# simple-loop-activevrs.net
KiCad netlist of a schematic drawn in EAGLE
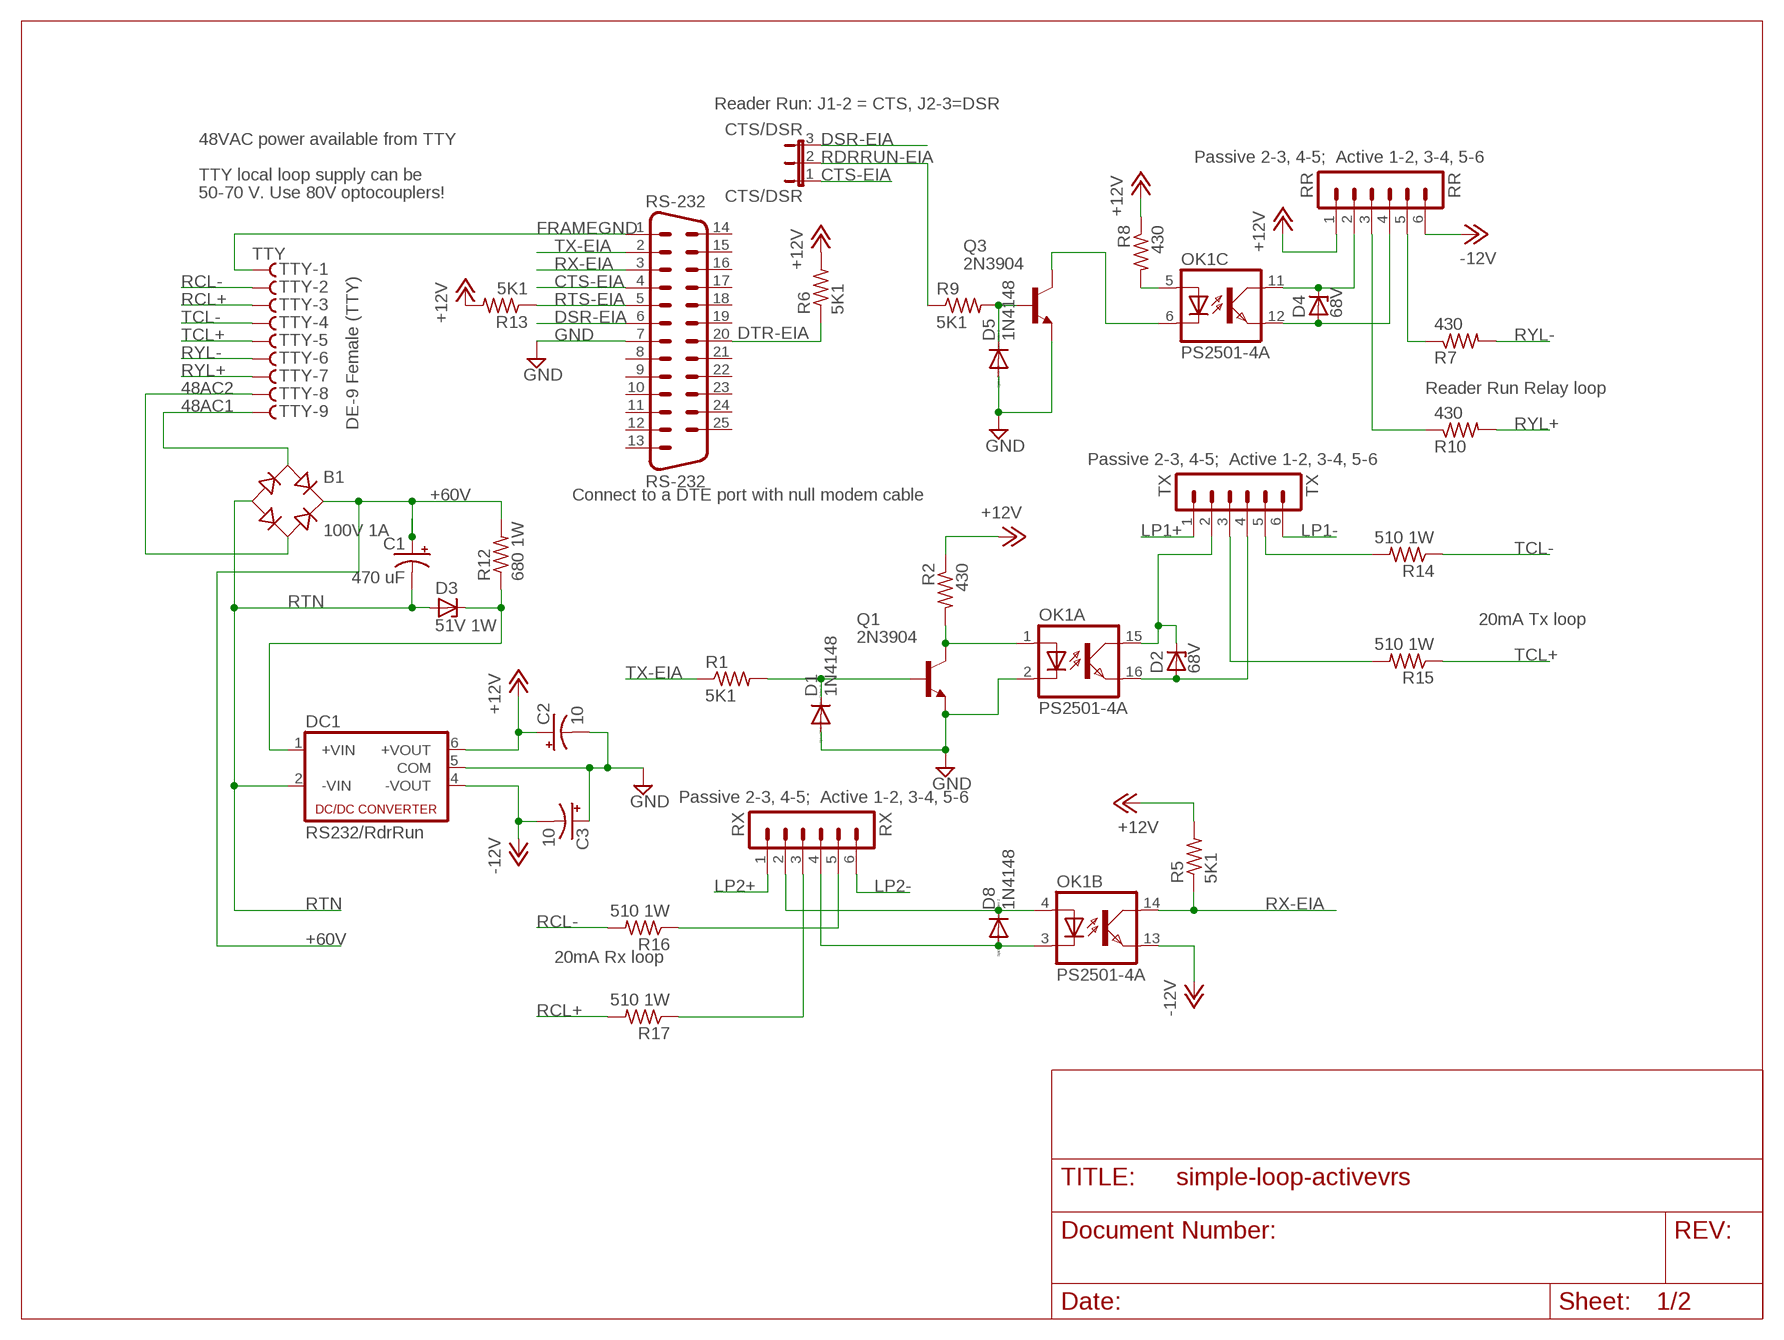
[diagram p0: schematic, sheet 1]
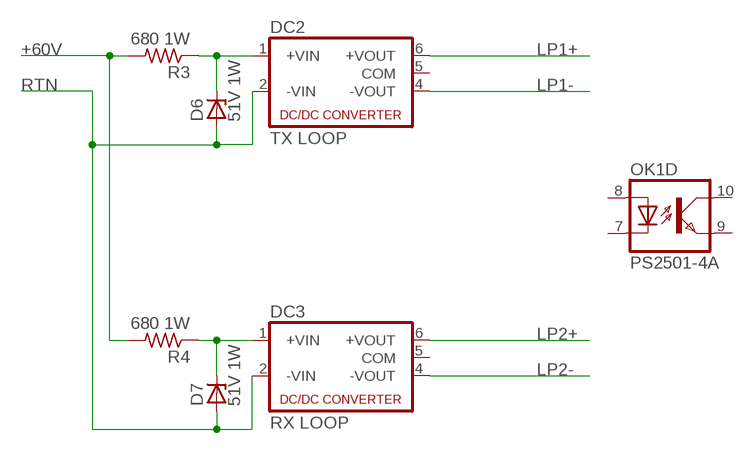
[diagram p1: schematic, sheet 2]

(export (version "E")
  (design (tool "Eeschema 10.0.6"))
  (components
    (comp (ref "D6")
      (value "51V 1W")
      (footprint "eagle-import:DO41Z10")
      (libsource (lib "eagle-import") (part "ZENER-DIODEDO41Z10"))
    )
    (comp (ref "D7")
      (value "51V 1W")
      (footprint "eagle-import:DO41Z10")
      (libsource (lib "eagle-import") (part "ZENER-DIODEDO41Z10"))
    )
    (comp (ref "DC2")
      (value "TX LOOP")
      (footprint "eagle-import:NMA")
      (fields (field (name "MF") "C & D TECHNOLOGIES, INC") (field (name "MPN") "NMA0515SC"))
      (libsource (lib "eagle-import") (part "NMA"))
    )
    (comp (ref "DC3")
      (value "RX LOOP")
      (footprint "eagle-import:NMA")
      (fields (field (name "MF") "C & D TECHNOLOGIES, INC") (field (name "MPN") "NMA0515SC"))
      (libsource (lib "eagle-import") (part "NMA"))
    )
    (comp (ref "OK1")
      (value "PS2501-4A")
      (footprint "eagle-import:DIL16")
      (fields (field (name "MF") "VISHAY/TELEFUNKEN") (field (name "MPN") "ILQ1"))
      (libsource (lib "eagle-import") (part "ILQ1"))
    )
    (comp (ref "R3")
      (value "680 1W")
      (footprint "eagle-import:P0817V")
      (libsource (lib "eagle-import") (part "R-US_0817/7V"))
    )
    (comp (ref "R4")
      (value "680 1W")
      (footprint "eagle-import:P0817V")
      (libsource (lib "eagle-import") (part "R-US_0817/7V"))
    )
    (comp (ref "B1")
      (value "100V 1A")
      (footprint "eagle-import:RB1A")
      (libsource (lib "eagle-import") (part "RB1A"))
    )
    (comp (ref "C1")
      (value "470 uF")
      (footprint "eagle-import:E7,5-18")
      (libsource (lib "eagle-import") (part "CPOL-USE7.5-18"))
    )
    (comp (ref "C2")
      (value "10")
      (footprint "eagle-import:B45181A")
      (libsource (lib "eagle-import") (part "CPOL-USB45181A"))
    )
    (comp (ref "C3")
      (value "10")
      (footprint "eagle-import:B45181A")
      (libsource (lib "eagle-import") (part "CPOL-USB45181A"))
    )
    (comp (ref "CTS/DSR")
      (value "CTS/DSR")
      (footprint "eagle-import:JP2")
      (libsource (lib "eagle-import") (part "JP2E"))
    )
    (comp (ref "D1")
      (value "1N4148")
      (footprint "eagle-import:DO35-10")
      (libsource (lib "eagle-import") (part "1N4148DO35-10"))
    )
    (comp (ref "D2")
      (value "68V")
      (footprint "eagle-import:DO41Z10")
      (libsource (lib "eagle-import") (part "ZENER-DIODEDO41Z10"))
    )
    (comp (ref "D3")
      (value "51V 1W")
      (footprint "eagle-import:DO41Z10")
      (libsource (lib "eagle-import") (part "ZENER-DIODEDO41Z10"))
    )
    (comp (ref "D4")
      (value "68V")
      (footprint "eagle-import:DO41Z10")
      (libsource (lib "eagle-import") (part "ZENER-DIODEDO41Z10"))
    )
    (comp (ref "D5")
      (value "1N4148")
      (footprint "eagle-import:DO35-10")
      (libsource (lib "eagle-import") (part "1N4148DO35-10"))
    )
    (comp (ref "D8")
      (value "1N4148")
      (footprint "eagle-import:DO35-10")
      (libsource (lib "eagle-import") (part "1N4148DO35-10"))
    )
    (comp (ref "DC1")
      (value "RS232/RdrRun")
      (footprint "eagle-import:NMA")
      (fields (field (name "MF") "C & D TECHNOLOGIES, INC") (field (name "MPN") "NMA0515SC"))
      (libsource (lib "eagle-import") (part "NMA"))
    )
    (comp (ref "Q1")
      (value "2N3904")
      (footprint "eagle-import:TO92")
      (libsource (lib "eagle-import") (part "2N3904"))
    )
    (comp (ref "Q3")
      (value "2N3904")
      (footprint "eagle-import:TO92")
      (libsource (lib "eagle-import") (part "2N3904"))
    )
    (comp (ref "R1")
      (value "5K1")
      (footprint "eagle-import:0207_10")
      (libsource (lib "eagle-import") (part "R-US_0207/10"))
    )
    (comp (ref "R2")
      (value "430")
      (footprint "eagle-import:0207_10")
      (libsource (lib "eagle-import") (part "R-US_0207/10"))
    )
    (comp (ref "R5")
      (value "5K1")
      (footprint "eagle-import:0207_10")
      (libsource (lib "eagle-import") (part "R-US_0207/10"))
    )
    (comp (ref "R6")
      (value "5K1")
      (footprint "eagle-import:0207_10")
      (libsource (lib "eagle-import") (part "R-US_0207/10"))
    )
    (comp (ref "R7")
      (value "430")
      (footprint "eagle-import:0207_10")
      (libsource (lib "eagle-import") (part "R-US_0207/10"))
    )
    (comp (ref "R8")
      (value "430")
      (footprint "eagle-import:0207_10")
      (libsource (lib "eagle-import") (part "R-US_0207/10"))
    )
    (comp (ref "R9")
      (value "5K1")
      (footprint "eagle-import:0207_10")
      (libsource (lib "eagle-import") (part "R-US_0207/10"))
    )
    (comp (ref "R10")
      (value "430")
      (footprint "eagle-import:0207_10")
      (libsource (lib "eagle-import") (part "R-US_0207/10"))
    )
    (comp (ref "R12")
      (value "680 1W")
      (footprint "eagle-import:P0817V")
      (libsource (lib "eagle-import") (part "R-US_0817/7V"))
    )
    (comp (ref "R13")
      (value "5K1")
      (footprint "eagle-import:0207_10")
      (libsource (lib "eagle-import") (part "R-US_0207/10"))
    )
    (comp (ref "R14")
      (value "510 1W")
      (footprint "eagle-import:P0817V")
      (libsource (lib "eagle-import") (part "R-US_0817/7V"))
    )
    (comp (ref "R15")
      (value "510 1W")
      (footprint "eagle-import:P0817V")
      (libsource (lib "eagle-import") (part "R-US_0817/7V"))
    )
    (comp (ref "R16")
      (value "510 1W")
      (footprint "eagle-import:P0817V")
      (libsource (lib "eagle-import") (part "R-US_0817/7V"))
    )
    (comp (ref "R17")
      (value "510 1W")
      (footprint "eagle-import:P0817V")
      (libsource (lib "eagle-import") (part "R-US_0817/7V"))
    )
    (comp (ref "RR")
      (value "RR")
      (footprint "eagle-import:MA06-1")
      (libsource (lib "eagle-import") (part "MA06-1"))
    )
    (comp (ref "RS-232")
      (value "RS-232")
      (footprint "eagle-import:M25H")
      (libsource (lib "eagle-import") (part "M25H"))
    )
    (comp (ref "RX")
      (value "RX")
      (footprint "eagle-import:MA06-1")
      (libsource (lib "eagle-import") (part "MA06-1"))
    )
    (comp (ref "TTY")
      (value "TTY")
      (footprint "eagle-import:F09H")
      (libsource (lib "eagle-import") (part "F09?SH"))
    )
    (comp (ref "TX")
      (value "TX")
      (footprint "eagle-import:MA06-1")
      (libsource (lib "eagle-import") (part "MA06-1"))
    )
  )
  (nets
    (net (code "1") (name "+12V") (class "Default")
      (node (ref "C2") (pin "+") (pinfunction "+_+") (pintype "passive"))
      (node (ref "DC1") (pin "6") (pinfunction "+VOUT_6") (pintype "passive"))
      (node (ref "R13") (pin "2") (pinfunction "2_2") (pintype "passive"))
      (node (ref "R2") (pin "1") (pinfunction "1_1") (pintype "passive"))
      (node (ref "R5") (pin "2") (pinfunction "2_2") (pintype "passive"))
      (node (ref "R6") (pin "2") (pinfunction "2_2") (pintype "passive"))
      (node (ref "R8") (pin "1") (pinfunction "1_1") (pintype "passive"))
      (node (ref "RR") (pin "1") (pinfunction "1_1") (pintype "passive"))
    )
    (net (code "2") (name "+60V") (class "Default")
      (node (ref "B1") (pin "+") (pinfunction "+_+") (pintype "passive"))
      (node (ref "C1") (pin "+") (pinfunction "+_+") (pintype "passive"))
      (node (ref "R12") (pin "2") (pinfunction "2_2") (pintype "passive"))
      (node (ref "R3") (pin "2") (pinfunction "2_2") (pintype "passive"))
      (node (ref "R4") (pin "2") (pinfunction "2_2") (pintype "passive"))
    )
    (net (code "3") (name "-12V") (class "Default")
      (node (ref "C3") (pin "-") (pinfunction "-_-") (pintype "passive"))
      (node (ref "DC1") (pin "4") (pinfunction "-VOUT_4") (pintype "passive"))
      (node (ref "OK1") (pin "13") (pinfunction "EMIT_13") (pintype "passive"))
      (node (ref "RR") (pin "6") (pinfunction "6_6") (pintype "passive"))
    )
    (net (code "4") (name "48AC1") (class "Default")
      (node (ref "B1") (pin "AC1") (pinfunction "AC1_AC1") (pintype "passive"))
      (node (ref "TTY") (pin "9") (pinfunction "F_9") (pintype "passive"))
    )
    (net (code "5") (name "48AC2") (class "Default")
      (node (ref "B1") (pin "AC2") (pinfunction "AC2_AC2") (pintype "passive"))
      (node (ref "TTY") (pin "8") (pinfunction "F_8") (pintype "passive"))
    )
    (net (code "6") (name "CTS-EIA") (class "Default")
      (node (ref "CTS/DSR") (pin "1") (pinfunction "1_1") (pintype "passive"))
      (node (ref "RS-232") (pin "4") (pinfunction "4_4") (pintype "passive"))
    )
    (net (code "7") (name "DSR-EIA") (class "Default")
      (node (ref "CTS/DSR") (pin "3") (pinfunction "3_3") (pintype "passive"))
      (node (ref "RS-232") (pin "6") (pinfunction "6_6") (pintype "passive"))
    )
    (net (code "8") (name "DTR-EIA") (class "Default")
      (node (ref "R6") (pin "1") (pinfunction "1_1") (pintype "passive"))
      (node (ref "RS-232") (pin "20") (pinfunction "20_20") (pintype "passive"))
    )
    (net (code "9") (name "FRAMEGND") (class "Default")
      (node (ref "RS-232") (pin "1") (pinfunction "1_1") (pintype "passive"))
      (node (ref "TTY") (pin "1") (pinfunction "F_1") (pintype "passive"))
    )
    (net (code "10") (name "GND") (class "Default")
      (node (ref "C2") (pin "-") (pinfunction "-_-") (pintype "passive"))
      (node (ref "C3") (pin "+") (pinfunction "+_+") (pintype "passive"))
      (node (ref "D1") (pin "A") (pinfunction "A_A") (pintype "passive"))
      (node (ref "D5") (pin "A") (pinfunction "A_A") (pintype "passive"))
      (node (ref "DC1") (pin "5") (pinfunction "COM_5") (pintype "passive"))
      (node (ref "OK1") (pin "2") (pinfunction "C_2") (pintype "passive"))
      (node (ref "Q1") (pin "3") (pinfunction "E_3") (pintype "passive"))
      (node (ref "Q3") (pin "3") (pinfunction "E_3") (pintype "passive"))
      (node (ref "RS-232") (pin "7") (pinfunction "7_7") (pintype "passive"))
    )
    (net (code "11") (name "LP1+") (class "Default")
      (node (ref "DC2") (pin "6") (pinfunction "+VOUT_6") (pintype "passive"))
      (node (ref "TX") (pin "1") (pinfunction "1_1") (pintype "passive"))
    )
    (net (code "12") (name "LP1-") (class "Default")
      (node (ref "DC2") (pin "4") (pinfunction "-VOUT_4") (pintype "passive"))
      (node (ref "TX") (pin "6") (pinfunction "6_6") (pintype "passive"))
    )
    (net (code "13") (name "LP2+") (class "Default")
      (node (ref "DC3") (pin "6") (pinfunction "+VOUT_6") (pintype "passive"))
      (node (ref "RX") (pin "1") (pinfunction "1_1") (pintype "passive"))
    )
    (net (code "14") (name "LP2-") (class "Default")
      (node (ref "DC3") (pin "4") (pinfunction "-VOUT_4") (pintype "passive"))
      (node (ref "RX") (pin "6") (pinfunction "6_6") (pintype "passive"))
    )
    (net (code "15") (name "Net-(DC1-+VIN)") (class "Default")
      (node (ref "D3") (pin "C") (pinfunction "C_C") (pintype "passive"))
      (node (ref "DC1") (pin "1") (pinfunction "+VIN_1") (pintype "passive"))
      (node (ref "R12") (pin "1") (pinfunction "1_1") (pintype "passive"))
    )
    (net (code "16") (name "Net-(DC2-+VIN)") (class "Default")
      (node (ref "D6") (pin "C") (pinfunction "C_C") (pintype "passive"))
      (node (ref "DC2") (pin "1") (pinfunction "+VIN_1") (pintype "passive"))
      (node (ref "R3") (pin "1") (pinfunction "1_1") (pintype "passive"))
    )
    (net (code "17") (name "Net-(DC3-+VIN)") (class "Default")
      (node (ref "D7") (pin "C") (pinfunction "C_C") (pintype "passive"))
      (node (ref "DC3") (pin "1") (pinfunction "+VIN_1") (pintype "passive"))
      (node (ref "R4") (pin "1") (pinfunction "1_1") (pintype "passive"))
    )
    (net (code "18") (name "Net-(OK1A-A)") (class "Default")
      (node (ref "OK1") (pin "1") (pinfunction "A_1") (pintype "passive"))
      (node (ref "Q1") (pin "1") (pinfunction "C_1") (pintype "passive"))
      (node (ref "R2") (pin "2") (pinfunction "2_2") (pintype "passive"))
    )
    (net (code "19") (name "Net-(OK1A-COL)") (class "Default")
      (node (ref "D2") (pin "C") (pinfunction "C_C") (pintype "passive"))
      (node (ref "OK1") (pin "15") (pinfunction "COL_15") (pintype "passive"))
      (node (ref "TX") (pin "2") (pinfunction "2_2") (pintype "passive"))
    )
    (net (code "20") (name "Net-(OK1A-EMIT)") (class "Default")
      (node (ref "D2") (pin "A") (pinfunction "A_A") (pintype "passive"))
      (node (ref "OK1") (pin "16") (pinfunction "EMIT_16") (pintype "passive"))
      (node (ref "TX") (pin "4") (pinfunction "4_4") (pintype "passive"))
    )
    (net (code "21") (name "Net-(OK1B-A)") (class "Default")
      (node (ref "D8") (pin "C") (pinfunction "C_C") (pintype "passive"))
      (node (ref "OK1") (pin "4") (pinfunction "A_4") (pintype "passive"))
      (node (ref "RX") (pin "2") (pinfunction "2_2") (pintype "passive"))
    )
    (net (code "22") (name "Net-(OK1B-C)") (class "Default")
      (node (ref "D8") (pin "A") (pinfunction "A_A") (pintype "passive"))
      (node (ref "OK1") (pin "3") (pinfunction "C_3") (pintype "passive"))
      (node (ref "RX") (pin "4") (pinfunction "4_4") (pintype "passive"))
    )
    (net (code "23") (name "Net-(OK1C-A)") (class "Default")
      (node (ref "OK1") (pin "5") (pinfunction "A_5") (pintype "passive"))
      (node (ref "R8") (pin "2") (pinfunction "2_2") (pintype "passive"))
    )
    (net (code "24") (name "Net-(OK1C-C)") (class "Default")
      (node (ref "OK1") (pin "6") (pinfunction "C_6") (pintype "passive"))
      (node (ref "Q3") (pin "1") (pinfunction "C_1") (pintype "passive"))
    )
    (net (code "25") (name "Net-(OK1C-COL)") (class "Default")
      (node (ref "D4") (pin "C") (pinfunction "C_C") (pintype "passive"))
      (node (ref "OK1") (pin "11") (pinfunction "COL_11") (pintype "passive"))
      (node (ref "RR") (pin "2") (pinfunction "2_2") (pintype "passive"))
    )
    (net (code "26") (name "Net-(OK1C-EMIT)") (class "Default")
      (node (ref "D4") (pin "A") (pinfunction "A_A") (pintype "passive"))
      (node (ref "OK1") (pin "12") (pinfunction "EMIT_12") (pintype "passive"))
      (node (ref "RR") (pin "4") (pinfunction "4_4") (pintype "passive"))
    )
    (net (code "27") (name "Net-(Q1-B)") (class "Default")
      (node (ref "D1") (pin "C") (pinfunction "C_C") (pintype "passive"))
      (node (ref "Q1") (pin "2") (pinfunction "B_2") (pintype "passive"))
      (node (ref "R1") (pin "2") (pinfunction "2_2") (pintype "passive"))
    )
    (net (code "28") (name "Net-(Q3-B)") (class "Default")
      (node (ref "D5") (pin "C") (pinfunction "C_C") (pintype "passive"))
      (node (ref "Q3") (pin "2") (pinfunction "B_2") (pintype "passive"))
      (node (ref "R9") (pin "2") (pinfunction "2_2") (pintype "passive"))
    )
    (net (code "29") (name "Net-(R7-Pad1)") (class "Default")
      (node (ref "R7") (pin "1") (pinfunction "1_1") (pintype "passive"))
      (node (ref "RR") (pin "5") (pinfunction "5_5") (pintype "passive"))
    )
    (net (code "30") (name "Net-(R10-Pad1)") (class "Default")
      (node (ref "R10") (pin "1") (pinfunction "1_1") (pintype "passive"))
      (node (ref "RR") (pin "3") (pinfunction "3_3") (pintype "passive"))
    )
    (net (code "31") (name "Net-(R14-Pad2)") (class "Default")
      (node (ref "R14") (pin "2") (pinfunction "2_2") (pintype "passive"))
      (node (ref "TX") (pin "5") (pinfunction "5_5") (pintype "passive"))
    )
    (net (code "32") (name "Net-(R15-Pad2)") (class "Default")
      (node (ref "R15") (pin "2") (pinfunction "2_2") (pintype "passive"))
      (node (ref "TX") (pin "3") (pinfunction "3_3") (pintype "passive"))
    )
    (net (code "33") (name "Net-(R16-Pad1)") (class "Default")
      (node (ref "R16") (pin "1") (pinfunction "1_1") (pintype "passive"))
      (node (ref "RX") (pin "5") (pinfunction "5_5") (pintype "passive"))
    )
    (net (code "34") (name "Net-(R17-Pad1)") (class "Default")
      (node (ref "R17") (pin "1") (pinfunction "1_1") (pintype "passive"))
      (node (ref "RX") (pin "3") (pinfunction "3_3") (pintype "passive"))
    )
    (net (code "35") (name "RCL+") (class "Default")
      (node (ref "R17") (pin "2") (pinfunction "2_2") (pintype "passive"))
      (node (ref "TTY") (pin "3") (pinfunction "F_3") (pintype "passive"))
    )
    (net (code "36") (name "RCL-") (class "Default")
      (node (ref "R16") (pin "2") (pinfunction "2_2") (pintype "passive"))
      (node (ref "TTY") (pin "2") (pinfunction "F_2") (pintype "passive"))
    )
    (net (code "37") (name "RDRRUN-EIA") (class "Default")
      (node (ref "CTS/DSR") (pin "2") (pinfunction "2_2") (pintype "passive"))
      (node (ref "R9") (pin "1") (pinfunction "1_1") (pintype "passive"))
    )
    (net (code "38") (name "RTN") (class "Default")
      (node (ref "B1") (pin "-") (pinfunction "-_-") (pintype "passive"))
      (node (ref "C1") (pin "-") (pinfunction "-_-") (pintype "passive"))
      (node (ref "D3") (pin "A") (pinfunction "A_A") (pintype "passive"))
      (node (ref "D6") (pin "A") (pinfunction "A_A") (pintype "passive"))
      (node (ref "D7") (pin "A") (pinfunction "A_A") (pintype "passive"))
      (node (ref "DC1") (pin "2") (pinfunction "-VIN_2") (pintype "passive"))
      (node (ref "DC2") (pin "2") (pinfunction "-VIN_2") (pintype "passive"))
      (node (ref "DC3") (pin "2") (pinfunction "-VIN_2") (pintype "passive"))
    )
    (net (code "39") (name "RTS-EIA") (class "Default")
      (node (ref "R13") (pin "1") (pinfunction "1_1") (pintype "passive"))
      (node (ref "RS-232") (pin "5") (pinfunction "5_5") (pintype "passive"))
    )
    (net (code "40") (name "RX-EIA") (class "Default")
      (node (ref "OK1") (pin "14") (pinfunction "COL_14") (pintype "passive"))
      (node (ref "R5") (pin "1") (pinfunction "1_1") (pintype "passive"))
      (node (ref "RS-232") (pin "3") (pinfunction "3_3") (pintype "passive"))
    )
    (net (code "41") (name "RYL+") (class "Default")
      (node (ref "R10") (pin "2") (pinfunction "2_2") (pintype "passive"))
      (node (ref "TTY") (pin "7") (pinfunction "F_7") (pintype "passive"))
    )
    (net (code "42") (name "RYL-") (class "Default")
      (node (ref "R7") (pin "2") (pinfunction "2_2") (pintype "passive"))
      (node (ref "TTY") (pin "6") (pinfunction "F_6") (pintype "passive"))
    )
    (net (code "43") (name "TCL+") (class "Default")
      (node (ref "R15") (pin "1") (pinfunction "1_1") (pintype "passive"))
      (node (ref "TTY") (pin "5") (pinfunction "F_5") (pintype "passive"))
    )
    (net (code "44") (name "TCL-") (class "Default")
      (node (ref "R14") (pin "1") (pinfunction "1_1") (pintype "passive"))
      (node (ref "TTY") (pin "4") (pinfunction "F_4") (pintype "passive"))
    )
    (net (code "45") (name "TX-EIA") (class "Default")
      (node (ref "R1") (pin "1") (pinfunction "1_1") (pintype "passive"))
      (node (ref "RS-232") (pin "2") (pinfunction "2_2") (pintype "passive"))
    )
    (net (code "46") (name "unconnected-(DC2-COM-Pad5)") (class "Default")
      (node (ref "DC2") (pin "5") (pinfunction "COM_5") (pintype "passive"))
    )
    (net (code "47") (name "unconnected-(DC3-COM-Pad5)") (class "Default")
      (node (ref "DC3") (pin "5") (pinfunction "COM_5") (pintype "passive"))
    )
    (net (code "48") (name "unconnected-(OK1D-A-Pad8)") (class "Default")
      (node (ref "OK1") (pin "8") (pinfunction "A_8") (pintype "passive"))
    )
    (net (code "49") (name "unconnected-(OK1D-C-Pad7)") (class "Default")
      (node (ref "OK1") (pin "7") (pinfunction "C_7") (pintype "passive"))
    )
    (net (code "50") (name "unconnected-(OK1D-COL-Pad10)") (class "Default")
      (node (ref "OK1") (pin "10") (pinfunction "COL_10") (pintype "passive"))
    )
    (net (code "51") (name "unconnected-(OK1D-EMIT-Pad9)") (class "Default")
      (node (ref "OK1") (pin "9") (pinfunction "EMIT_9") (pintype "passive"))
    )
    (net (code "52") (name "unconnected-(RS-232-Pad8)") (class "Default")
      (node (ref "RS-232") (pin "8") (pinfunction "8_8") (pintype "passive"))
    )
    (net (code "53") (name "unconnected-(RS-232-Pad9)") (class "Default")
      (node (ref "RS-232") (pin "9") (pinfunction "9_9") (pintype "passive"))
    )
    (net (code "54") (name "unconnected-(RS-232-Pad10)") (class "Default")
      (node (ref "RS-232") (pin "10") (pinfunction "10_10") (pintype "passive"))
    )
    (net (code "55") (name "unconnected-(RS-232-Pad11)") (class "Default")
      (node (ref "RS-232") (pin "11") (pinfunction "11_11") (pintype "passive"))
    )
    (net (code "56") (name "unconnected-(RS-232-Pad12)") (class "Default")
      (node (ref "RS-232") (pin "12") (pinfunction "12_12") (pintype "passive"))
    )
    (net (code "57") (name "unconnected-(RS-232-Pad13)") (class "Default")
      (node (ref "RS-232") (pin "13") (pinfunction "13_13") (pintype "passive"))
    )
    (net (code "58") (name "unconnected-(RS-232-Pad14)") (class "Default")
      (node (ref "RS-232") (pin "14") (pinfunction "14_14") (pintype "passive"))
    )
    (net (code "59") (name "unconnected-(RS-232-Pad15)") (class "Default")
      (node (ref "RS-232") (pin "15") (pinfunction "15_15") (pintype "passive"))
    )
    (net (code "60") (name "unconnected-(RS-232-Pad16)") (class "Default")
      (node (ref "RS-232") (pin "16") (pinfunction "16_16") (pintype "passive"))
    )
    (net (code "61") (name "unconnected-(RS-232-Pad17)") (class "Default")
      (node (ref "RS-232") (pin "17") (pinfunction "17_17") (pintype "passive"))
    )
    (net (code "62") (name "unconnected-(RS-232-Pad18)") (class "Default")
      (node (ref "RS-232") (pin "18") (pinfunction "18_18") (pintype "passive"))
    )
    (net (code "63") (name "unconnected-(RS-232-Pad19)") (class "Default")
      (node (ref "RS-232") (pin "19") (pinfunction "19_19") (pintype "passive"))
    )
    (net (code "64") (name "unconnected-(RS-232-Pad21)") (class "Default")
      (node (ref "RS-232") (pin "21") (pinfunction "21_21") (pintype "passive"))
    )
    (net (code "65") (name "unconnected-(RS-232-Pad22)") (class "Default")
      (node (ref "RS-232") (pin "22") (pinfunction "22_22") (pintype "passive"))
    )
    (net (code "66") (name "unconnected-(RS-232-Pad23)") (class "Default")
      (node (ref "RS-232") (pin "23") (pinfunction "23_23") (pintype "passive"))
    )
    (net (code "67") (name "unconnected-(RS-232-Pad24)") (class "Default")
      (node (ref "RS-232") (pin "24") (pinfunction "24_24") (pintype "passive"))
    )
    (net (code "68") (name "unconnected-(RS-232-Pad25)") (class "Default")
      (node (ref "RS-232") (pin "25") (pinfunction "25_25") (pintype "passive"))
    )
  )
)
